# remote.net
KiCad netlist of a schematic drawn in EAGLE
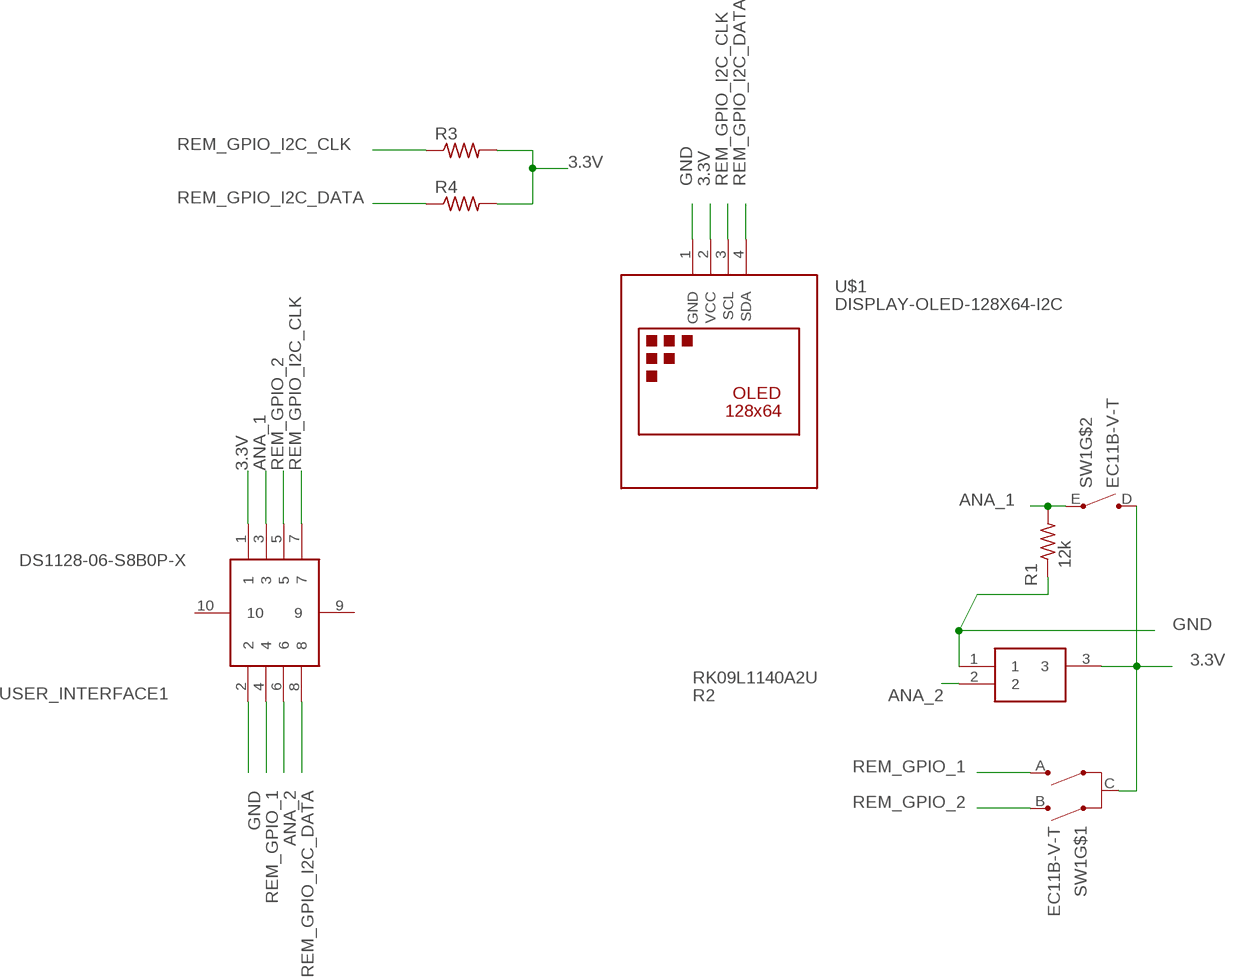
[diagram p0: schematic, sheet 1]

(export (version "E")
  (design (tool "Eeschema 10.0.6"))
  (components
    (comp (ref "R1")
      (value "12k")
      (footprint "eagle-import:R0805")
      (libsource (lib "eagle-import") (part "R-US_R0805"))
    )
    (comp (ref "R2")
      (value "RK09L1140A2U")
      (footprint "eagle-import:RK09L1140A5E")
      (fields (field (name "MOUSER_PART_NUMBER") "688-RK09L1140A2U"))
      (libsource (lib "eagle-import") (part "RK09L1140A2U"))
    )
    (comp (ref "R3")
      (value "R-US_R0805")
      (footprint "eagle-import:R0805")
      (libsource (lib "eagle-import") (part "R-US_R0805"))
    )
    (comp (ref "R4")
      (value "R-US_R0805")
      (footprint "eagle-import:R0805")
      (libsource (lib "eagle-import") (part "R-US_R0805"))
    )
    (comp (ref "SW1")
      (value "EC11B-V-T")
      (footprint "eagle-import:EC11B-V")
      (libsource (lib "eagle-import") (part "EC11B-V-T"))
    )
    (comp (ref "U$1")
      (value "DISPLAY-OLED-128X64-I2C")
      (footprint "eagle-import:DISPLAY-OLED-128X64-I2C")
      (libsource (lib "eagle-import") (part "DISPLAY-OLED-128X64-I2C"))
    )
    (comp (ref "USER_INTERFACE1")
      (value "DS1128-06-S8B0P-X")
      (footprint "eagle-import:DS112806S8B0PX")
      (libsource (lib "eagle-import") (part "DS1128-06-S8B0P-X"))
    )
  )
  (nets
    (net (code "1") (name "3.3V") (class "Default")
      (node (ref "R2") (pin "3") (pinfunction "3_3") (pintype "bidirectional"))
      (node (ref "R3") (pin "2") (pinfunction "2_2") (pintype "passive"))
      (node (ref "R4") (pin "2") (pinfunction "2_2") (pintype "passive"))
      (node (ref "SW1") (pin "C") (pinfunction "C_C") (pintype "passive"))
      (node (ref "SW1") (pin "D") (pinfunction "D_D") (pintype "passive"))
      (node (ref "U$1") (pin "2") (pinfunction "VCC_2") (pintype "power_in"))
      (node (ref "USER_INTERFACE1") (pin "1") (pinfunction "1_1") (pintype "bidirectional"))
    )
    (net (code "2") (name "ANA_1") (class "Default")
      (node (ref "R1") (pin "2") (pinfunction "2_2") (pintype "passive"))
      (node (ref "SW1") (pin "E") (pinfunction "E_E") (pintype "passive"))
      (node (ref "USER_INTERFACE1") (pin "3") (pinfunction "3_3") (pintype "bidirectional"))
    )
    (net (code "3") (name "ANA_2") (class "Default")
      (node (ref "R2") (pin "2") (pinfunction "2_2") (pintype "bidirectional"))
      (node (ref "USER_INTERFACE1") (pin "6") (pinfunction "6_6") (pintype "bidirectional"))
    )
    (net (code "4") (name "GND") (class "Default")
      (node (ref "R1") (pin "1") (pinfunction "1_1") (pintype "passive"))
      (node (ref "R2") (pin "1") (pinfunction "1_1") (pintype "bidirectional"))
      (node (ref "U$1") (pin "1") (pinfunction "GND_1") (pintype "power_in"))
      (node (ref "USER_INTERFACE1") (pin "2") (pinfunction "2_2") (pintype "bidirectional"))
    )
    (net (code "5") (name "REM_GPIO_1") (class "Default")
      (node (ref "SW1") (pin "A") (pinfunction "A_A") (pintype "passive"))
      (node (ref "USER_INTERFACE1") (pin "4") (pinfunction "4_4") (pintype "bidirectional"))
    )
    (net (code "6") (name "REM_GPIO_2") (class "Default")
      (node (ref "SW1") (pin "B") (pinfunction "B_B") (pintype "passive"))
      (node (ref "USER_INTERFACE1") (pin "5") (pinfunction "5_5") (pintype "bidirectional"))
    )
    (net (code "7") (name "REM_GPIO_I2C_CLK") (class "Default")
      (node (ref "R3") (pin "1") (pinfunction "1_1") (pintype "passive"))
      (node (ref "U$1") (pin "3") (pinfunction "SCL_3") (pintype "bidirectional"))
      (node (ref "USER_INTERFACE1") (pin "7") (pinfunction "7_7") (pintype "bidirectional"))
    )
    (net (code "8") (name "REM_GPIO_I2C_DATA") (class "Default")
      (node (ref "R4") (pin "1") (pinfunction "1_1") (pintype "passive"))
      (node (ref "U$1") (pin "4") (pinfunction "SDA_4") (pintype "bidirectional"))
      (node (ref "USER_INTERFACE1") (pin "8") (pinfunction "8_8") (pintype "bidirectional"))
    )
    (net (code "9") (name "unconnected-(USER_INTERFACE1-Pad9)") (class "Default")
      (node (ref "USER_INTERFACE1") (pin "9") (pinfunction "9_9") (pintype "bidirectional"))
    )
    (net (code "10") (name "unconnected-(USER_INTERFACE1-Pad10)") (class "Default")
      (node (ref "USER_INTERFACE1") (pin "10") (pinfunction "10_10") (pintype "bidirectional"))
    )
  )
)
